# LogicSlice.net
KiCad netlist of a schematic drawn in EAGLE
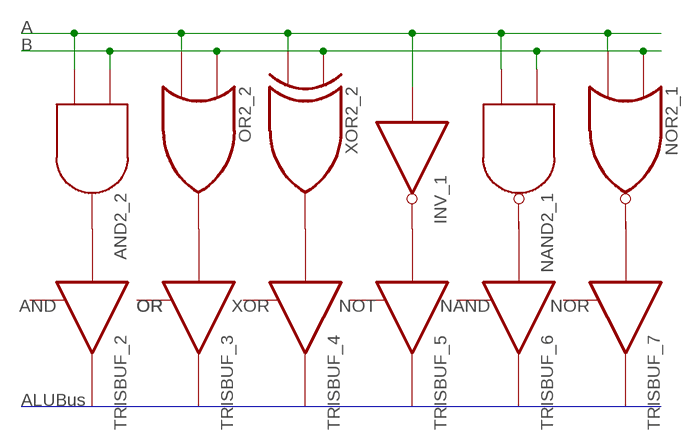
[diagram p0: schematic, sheet 1]

(export (version "E")
  (design (tool "Eeschema 10.0.6"))
  (components
    (comp (ref "AND2_2")
      (value "AND2")
      (footprint "eagle-import:3PIN")
      (libsource (lib "eagle-import") (part "AND2"))
    )
    (comp (ref "INV_1")
      (value "INV")
      (footprint "eagle-import:3PIN")
      (libsource (lib "eagle-import") (part "INV"))
    )
    (comp (ref "NAND2_1")
      (value "NAND2")
      (footprint "eagle-import:3PIN")
      (libsource (lib "eagle-import") (part "NAND2"))
    )
    (comp (ref "NOR2_1")
      (value "NOR2")
      (footprint "eagle-import:3PIN")
      (libsource (lib "eagle-import") (part "NOR2"))
    )
    (comp (ref "OR2_2")
      (value "OR2")
      (footprint "eagle-import:3PIN")
      (libsource (lib "eagle-import") (part "OR2"))
    )
    (comp (ref "TRISBUF_2")
      (value "TRISBUF")
      (footprint "eagle-import:3PIN")
      (libsource (lib "eagle-import") (part "TRISBUF"))
    )
    (comp (ref "TRISBUF_3")
      (value "TRISBUF")
      (footprint "eagle-import:3PIN")
      (libsource (lib "eagle-import") (part "TRISBUF"))
    )
    (comp (ref "TRISBUF_4")
      (value "TRISBUF")
      (footprint "eagle-import:3PIN")
      (libsource (lib "eagle-import") (part "TRISBUF"))
    )
    (comp (ref "TRISBUF_5")
      (value "TRISBUF")
      (footprint "eagle-import:3PIN")
      (libsource (lib "eagle-import") (part "TRISBUF"))
    )
    (comp (ref "TRISBUF_6")
      (value "TRISBUF")
      (footprint "eagle-import:3PIN")
      (libsource (lib "eagle-import") (part "TRISBUF"))
    )
    (comp (ref "TRISBUF_7")
      (value "TRISBUF")
      (footprint "eagle-import:3PIN")
      (libsource (lib "eagle-import") (part "TRISBUF"))
    )
    (comp (ref "XOR2_2")
      (value "XOR2")
      (footprint "eagle-import:3PIN")
      (libsource (lib "eagle-import") (part "XOR2"))
    )
  )
  (nets
    (net (code "1") (name "Net-(AND2_2-A)") (class "Default")
      (node (ref "AND2_2") (pin "P$1") (pinfunction "A_P$1") (pintype "input"))
      (node (ref "AND2_2") (pin "P$2") (pinfunction "I1_P$2") (pintype "input"))
      (node (ref "INV_1") (pin "P$1") (pinfunction "I_P$1") (pintype "input"))
      (node (ref "NAND2_1") (pin "P$1") (pinfunction "A_P$1") (pintype "input"))
      (node (ref "NAND2_1") (pin "P$2") (pinfunction "I1_P$2") (pintype "input"))
      (node (ref "NOR2_1") (pin "P$1") (pinfunction "I0_P$1") (pintype "input"))
      (node (ref "NOR2_1") (pin "P$2") (pinfunction "I1_P$2") (pintype "input"))
      (node (ref "OR2_2") (pin "P$1") (pinfunction "I0_P$1") (pintype "input"))
      (node (ref "OR2_2") (pin "P$2") (pinfunction "I1_P$2") (pintype "input"))
      (node (ref "XOR2_2") (pin "P$1") (pinfunction "I0_P$1") (pintype "input"))
      (node (ref "XOR2_2") (pin "P$2") (pinfunction "I1_P$2") (pintype "input"))
    )
    (net (code "2") (name "Net-(AND2_2-O)") (class "Default")
      (node (ref "AND2_2") (pin "P$3") (pinfunction "O_P$3") (pintype "output"))
      (node (ref "TRISBUF_2") (pin "P$1") (pinfunction "I_P$1") (pintype "input"))
    )
    (net (code "3") (name "Net-(INV_1-O)") (class "Default")
      (node (ref "INV_1") (pin "P$2") (pinfunction "O_P$2") (pintype "open_collector"))
      (node (ref "TRISBUF_5") (pin "P$1") (pinfunction "I_P$1") (pintype "input"))
    )
    (net (code "4") (name "Net-(NAND2_1-O)") (class "Default")
      (node (ref "NAND2_1") (pin "P$3") (pinfunction "O_P$3") (pintype "output"))
      (node (ref "TRISBUF_6") (pin "P$1") (pinfunction "I_P$1") (pintype "input"))
    )
    (net (code "5") (name "Net-(NOR2_1-O)") (class "Default")
      (node (ref "NOR2_1") (pin "P$3") (pinfunction "O_P$3") (pintype "output"))
      (node (ref "TRISBUF_7") (pin "P$1") (pinfunction "I_P$1") (pintype "input"))
    )
    (net (code "6") (name "Net-(OR2_2-O)") (class "Default")
      (node (ref "OR2_2") (pin "P$3") (pinfunction "O_P$3") (pintype "output"))
      (node (ref "TRISBUF_3") (pin "P$1") (pinfunction "I_P$1") (pintype "input"))
    )
    (net (code "7") (name "Net-(TRISBUF_4-I)") (class "Default")
      (node (ref "TRISBUF_4") (pin "P$1") (pinfunction "I_P$1") (pintype "input"))
      (node (ref "XOR2_2") (pin "P$3") (pinfunction "O_P$3") (pintype "output"))
    )
    (net (code "8") (name "unconnected-(TRISBUF_2-O-PadP$2)") (class "Default")
      (node (ref "TRISBUF_2") (pin "P$2") (pinfunction "O_P$2") (pintype "open_collector"))
    )
    (net (code "9") (name "unconnected-(TRISBUF_2-P$1-PadP$3)") (class "Default")
      (node (ref "TRISBUF_2") (pin "P$3") (pinfunction "P$1_P$3") (pintype "bidirectional"))
    )
    (net (code "10") (name "unconnected-(TRISBUF_3-O-PadP$2)") (class "Default")
      (node (ref "TRISBUF_3") (pin "P$2") (pinfunction "O_P$2") (pintype "open_collector"))
    )
    (net (code "11") (name "unconnected-(TRISBUF_3-P$1-PadP$3)") (class "Default")
      (node (ref "TRISBUF_3") (pin "P$3") (pinfunction "P$1_P$3") (pintype "bidirectional"))
    )
    (net (code "12") (name "unconnected-(TRISBUF_4-O-PadP$2)") (class "Default")
      (node (ref "TRISBUF_4") (pin "P$2") (pinfunction "O_P$2") (pintype "open_collector"))
    )
    (net (code "13") (name "unconnected-(TRISBUF_4-P$1-PadP$3)") (class "Default")
      (node (ref "TRISBUF_4") (pin "P$3") (pinfunction "P$1_P$3") (pintype "bidirectional"))
    )
    (net (code "14") (name "unconnected-(TRISBUF_5-O-PadP$2)") (class "Default")
      (node (ref "TRISBUF_5") (pin "P$2") (pinfunction "O_P$2") (pintype "open_collector"))
    )
    (net (code "15") (name "unconnected-(TRISBUF_5-P$1-PadP$3)") (class "Default")
      (node (ref "TRISBUF_5") (pin "P$3") (pinfunction "P$1_P$3") (pintype "bidirectional"))
    )
    (net (code "16") (name "unconnected-(TRISBUF_6-O-PadP$2)") (class "Default")
      (node (ref "TRISBUF_6") (pin "P$2") (pinfunction "O_P$2") (pintype "open_collector"))
    )
    (net (code "17") (name "unconnected-(TRISBUF_6-P$1-PadP$3)") (class "Default")
      (node (ref "TRISBUF_6") (pin "P$3") (pinfunction "P$1_P$3") (pintype "bidirectional"))
    )
    (net (code "18") (name "unconnected-(TRISBUF_7-O-PadP$2)") (class "Default")
      (node (ref "TRISBUF_7") (pin "P$2") (pinfunction "O_P$2") (pintype "open_collector"))
    )
    (net (code "19") (name "unconnected-(TRISBUF_7-P$1-PadP$3)") (class "Default")
      (node (ref "TRISBUF_7") (pin "P$3") (pinfunction "P$1_P$3") (pintype "bidirectional"))
    )
  )
)
